# obstacle_avoiding_robot.net
KiCad netlist of a schematic drawn in EAGLE
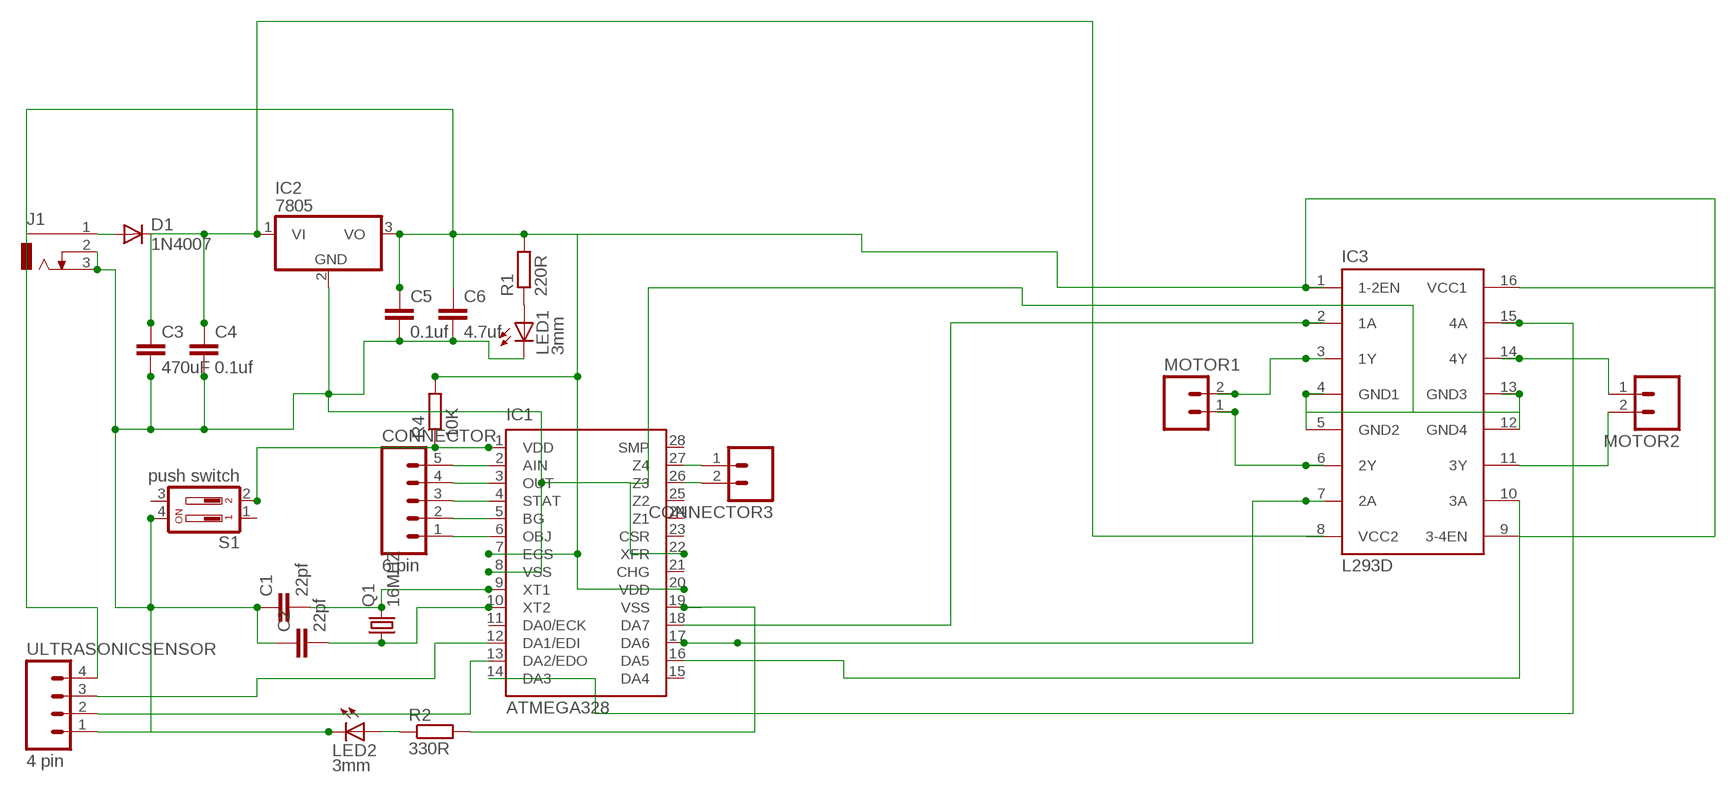
[diagram p0: schematic, sheet 1]

(export (version "E")
  (design (tool "Eeschema 10.0.6"))
  (components
    (comp (ref "C1")
      (value "22pf")
      (footprint "eagle-import:C2.5-2")
      (libsource (lib "eagle-import") (part "C2.5/2"))
    )
    (comp (ref "C2")
      (value "22pf")
      (footprint "eagle-import:C2.5-2")
      (libsource (lib "eagle-import") (part "C2.5/2"))
    )
    (comp (ref "C3")
      (value "470uF")
      (footprint "eagle-import:C2.5-2")
      (libsource (lib "eagle-import") (part "C2.5/2"))
    )
    (comp (ref "C4")
      (value "0.1uf")
      (footprint "eagle-import:C2.5-2")
      (libsource (lib "eagle-import") (part "C2.5/2"))
    )
    (comp (ref "C5")
      (value "0.1uf")
      (footprint "eagle-import:C2.5-2")
      (libsource (lib "eagle-import") (part "C2.5/2"))
    )
    (comp (ref "C6")
      (value "4.7uf")
      (footprint "eagle-import:C2.5-2")
      (libsource (lib "eagle-import") (part "C2.5/2"))
    )
    (comp (ref "CONNECTOR")
      (value "6 pin")
      (footprint "eagle-import:05P")
      (libsource (lib "eagle-import") (part "M05"))
    )
    (comp (ref "CONNECTOR3")
      (value "M02")
      (footprint "eagle-import:02P")
      (fields (field (name "OC_FARNELL") "unknown") (field (name "OC_NEWARK") "unknown"))
      (libsource (lib "eagle-import") (part "M02"))
    )
    (comp (ref "D1")
      (value "1N4007")
      (footprint "eagle-import:DO41-10")
      (libsource (lib "eagle-import") (part "1N4004"))
    )
    (comp (ref "IC1")
      (value "ATMEGA328")
      (footprint "eagle-import:DIL28-3")
      (libsource (lib "eagle-import") (part "QT9701BD"))
    )
    (comp (ref "IC2")
      (value "7805")
      (footprint "eagle-import:TO220V")
      (libsource (lib "eagle-import") (part "78TV6"))
    )
    (comp (ref "IC3")
      (value "L293D")
      (footprint "eagle-import:DIL16")
      (libsource (lib "eagle-import") (part "L293D"))
    )
    (comp (ref "J1")
      (value "DCJ0303")
      (footprint "eagle-import:DCJ0303")
      (libsource (lib "eagle-import") (part "DCJ0303"))
    )
    (comp (ref "LED1")
      (value "3mm")
      (footprint "eagle-import:LED3MM")
      (libsource (lib "eagle-import") (part "LED3MM"))
    )
    (comp (ref "LED2")
      (value "3mm")
      (footprint "eagle-import:LED3MM")
      (libsource (lib "eagle-import") (part "LED3MM"))
    )
    (comp (ref "MOTOR1")
      (value "M02")
      (footprint "eagle-import:02P")
      (fields (field (name "OC_FARNELL") "unknown") (field (name "OC_NEWARK") "unknown"))
      (libsource (lib "eagle-import") (part "M02"))
    )
    (comp (ref "MOTOR2")
      (value "M02")
      (footprint "eagle-import:02P")
      (libsource (lib "eagle-import") (part "M02"))
    )
    (comp (ref "Q1")
      (value "16MHZ")
      (footprint "eagle-import:HC49_S")
      (libsource (lib "eagle-import") (part "CRYSTALHC49S"))
    )
    (comp (ref "R1")
      (value "220R")
      (footprint "eagle-import:0207_10")
      (libsource (lib "eagle-import") (part "R-EU_0207/10"))
    )
    (comp (ref "R2")
      (value "330R")
      (footprint "eagle-import:0207_10")
      (libsource (lib "eagle-import") (part "R-EU_0207/10"))
    )
    (comp (ref "R4")
      (value "10K")
      (footprint "eagle-import:0207_10")
      (libsource (lib "eagle-import") (part "R-EU_0207/10"))
    )
    (comp (ref "S1")
      (value "push switch")
      (footprint "eagle-import:DP-02")
      (fields (field (name "MPN") "MCDP02"))
      (libsource (lib "eagle-import") (part "DP02"))
    )
    (comp (ref "ULTRASONICSENSOR")
      (value "4 pin")
      (footprint "eagle-import:04P")
      (fields (field (name "OC_FARNELL") "unknown") (field (name "OC_NEWARK") "unknown"))
      (libsource (lib "eagle-import") (part "M04"))
    )
  )
  (nets
    (net (code "1") (name "Net-(D1-PadA)") (class "Default")
      (node (ref "D1") (pin "A") (pinfunction "A_A") (pintype "passive"))
      (node (ref "J1") (pin "1") (pinfunction "1_1") (pintype "passive"))
    )
    (net (code "2") (name "Net-(IC1-AIN)") (class "Default")
      (node (ref "CONNECTOR") (pin "5") (pinfunction "5_5") (pintype "passive"))
      (node (ref "IC1") (pin "2") (pinfunction "AIN_2") (pintype "input"))
    )
    (net (code "3") (name "Net-(IC1-BG)") (class "Default")
      (node (ref "CONNECTOR") (pin "2") (pinfunction "2_2") (pintype "passive"))
      (node (ref "IC1") (pin "5") (pinfunction "BG_5") (pintype "input"))
    )
    (net (code "4") (name "Net-(IC1-DA1{slash}EDI)") (class "Default")
      (node (ref "IC1") (pin "12") (pinfunction "DA1/EDI_12") (pintype "output"))
      (node (ref "ULTRASONICSENSOR") (pin "3") (pinfunction "3_3") (pintype "passive"))
    )
    (net (code "5") (name "Net-(IC1-DA2{slash}EDO)") (class "Default")
      (node (ref "IC1") (pin "13") (pinfunction "DA2/EDO_13") (pintype "output"))
      (node (ref "ULTRASONICSENSOR") (pin "2") (pinfunction "2_2") (pintype "passive"))
    )
    (net (code "6") (name "Net-(IC1-DA3)") (class "Default")
      (node (ref "IC1") (pin "14") (pinfunction "DA3_14") (pintype "output"))
      (node (ref "IC3") (pin "15") (pinfunction "4A_15") (pintype "input"))
    )
    (net (code "7") (name "Net-(IC1-DA5)") (class "Default")
      (node (ref "IC1") (pin "16") (pinfunction "DA5_16") (pintype "output"))
      (node (ref "IC3") (pin "10") (pinfunction "3A_10") (pintype "input"))
    )
    (net (code "8") (name "Net-(IC1-DA6)") (class "Default")
      (node (ref "IC1") (pin "17") (pinfunction "DA6_17") (pintype "output"))
      (node (ref "IC3") (pin "7") (pinfunction "2A_7") (pintype "input"))
    )
    (net (code "9") (name "Net-(IC1-DA7)") (class "Default")
      (node (ref "IC1") (pin "18") (pinfunction "DA7_18") (pintype "output"))
      (node (ref "IC3") (pin "2") (pinfunction "1A_2") (pintype "input"))
    )
    (net (code "10") (name "Net-(IC1-ECS)") (class "Default")
      (node (ref "C5") (pin "1") (pinfunction "1_1") (pintype "passive"))
      (node (ref "C6") (pin "1") (pinfunction "1_1") (pintype "passive"))
      (node (ref "IC1") (pin "20") (pinfunction "VDD_20") (pintype "input"))
      (node (ref "IC1") (pin "7") (pinfunction "ECS_7") (pintype "output"))
      (node (ref "IC2") (pin "3") (pinfunction "VO_3") (pintype "passive"))
      (node (ref "IC3") (pin "1") (pinfunction "1-2EN_1") (pintype "input"))
      (node (ref "IC3") (pin "16") (pinfunction "VCC1_16") (pintype "power_in"))
      (node (ref "IC3") (pin "9") (pinfunction "3-4EN_9") (pintype "input"))
      (node (ref "R1") (pin "2") (pinfunction "2_2") (pintype "passive"))
      (node (ref "R4") (pin "2") (pinfunction "2_2") (pintype "passive"))
      (node (ref "ULTRASONICSENSOR") (pin "4") (pinfunction "4_4") (pintype "passive"))
    )
    (net (code "11") (name "Net-(IC1-OBJ)") (class "Default")
      (node (ref "CONNECTOR") (pin "1") (pinfunction "1_1") (pintype "passive"))
      (node (ref "IC1") (pin "6") (pinfunction "OBJ_6") (pintype "input"))
    )
    (net (code "12") (name "Net-(IC1-OUT)") (class "Default")
      (node (ref "CONNECTOR") (pin "4") (pinfunction "4_4") (pintype "passive"))
      (node (ref "IC1") (pin "3") (pinfunction "OUT_3") (pintype "output"))
    )
    (net (code "13") (name "Net-(IC1-STAT)") (class "Default")
      (node (ref "CONNECTOR") (pin "3") (pinfunction "3_3") (pintype "passive"))
      (node (ref "IC1") (pin "4") (pinfunction "STAT_4") (pintype "output"))
    )
    (net (code "14") (name "Net-(IC1-VDD-Pad1)") (class "Default")
      (node (ref "IC1") (pin "1") (pinfunction "VDD_1") (pintype "input"))
      (node (ref "R4") (pin "1") (pinfunction "1_1") (pintype "passive"))
      (node (ref "S1") (pin "2") (pinfunction "2_2") (pintype "passive"))
    )
    (net (code "15") (name "Net-(IC1-VSS-Pad19)") (class "Default")
      (node (ref "IC1") (pin "19") (pinfunction "VSS_19") (pintype "input"))
      (node (ref "R2") (pin "2") (pinfunction "2_2") (pintype "passive"))
    )
    (net (code "16") (name "Net-(IC1-XFR)") (class "Default")
      (node (ref "C1") (pin "1") (pinfunction "1_1") (pintype "passive"))
      (node (ref "C2") (pin "1") (pinfunction "1_1") (pintype "passive"))
      (node (ref "C3") (pin "2") (pinfunction "2_2") (pintype "passive"))
      (node (ref "C4") (pin "2") (pinfunction "2_2") (pintype "passive"))
      (node (ref "C5") (pin "2") (pinfunction "2_2") (pintype "passive"))
      (node (ref "C6") (pin "2") (pinfunction "2_2") (pintype "passive"))
      (node (ref "IC1") (pin "22") (pinfunction "XFR_22") (pintype "output"))
      (node (ref "IC1") (pin "8") (pinfunction "VSS_8") (pintype "input"))
      (node (ref "IC2") (pin "2") (pinfunction "GND_2") (pintype "passive"))
      (node (ref "IC3") (pin "12") (pinfunction "GND4_12") (pintype "power_in"))
      (node (ref "IC3") (pin "13") (pinfunction "GND3_13") (pintype "power_in"))
      (node (ref "IC3") (pin "4") (pinfunction "GND1_4") (pintype "power_in"))
      (node (ref "IC3") (pin "5") (pinfunction "GND2_5") (pintype "power_in"))
      (node (ref "J1") (pin "2") (pinfunction "2_2") (pintype "passive"))
      (node (ref "J1") (pin "3") (pinfunction "3_3") (pintype "passive"))
      (node (ref "LED1") (pin "K") (pinfunction "C_K") (pintype "passive"))
      (node (ref "LED2") (pin "K") (pinfunction "C_K") (pintype "passive"))
      (node (ref "S1") (pin "4") (pinfunction "4_4") (pintype "passive"))
      (node (ref "ULTRASONICSENSOR") (pin "1") (pinfunction "1_1") (pintype "passive"))
    )
    (net (code "17") (name "Net-(IC1-XT1)") (class "Default")
      (node (ref "C1") (pin "2") (pinfunction "2_2") (pintype "passive"))
      (node (ref "IC1") (pin "9") (pinfunction "XT1_9") (pintype "input"))
      (node (ref "Q1") (pin "2") (pinfunction "2_2") (pintype "passive"))
    )
    (net (code "18") (name "Net-(IC1-XT2)") (class "Default")
      (node (ref "C2") (pin "2") (pinfunction "2_2") (pintype "passive"))
      (node (ref "IC1") (pin "10") (pinfunction "XT2_10") (pintype "output"))
      (node (ref "Q1") (pin "1") (pinfunction "1_1") (pintype "passive"))
    )
    (net (code "19") (name "Net-(IC1-Z3)") (class "Default")
      (node (ref "CONNECTOR3") (pin "2") (pinfunction "2_2") (pintype "passive"))
      (node (ref "IC1") (pin "26") (pinfunction "Z3_26") (pintype "output"))
    )
    (net (code "20") (name "Net-(IC1-Z4)") (class "Default")
      (node (ref "CONNECTOR3") (pin "1") (pinfunction "1_1") (pintype "passive"))
      (node (ref "IC1") (pin "27") (pinfunction "Z4_27") (pintype "output"))
    )
    (net (code "21") (name "Net-(IC2-VI)") (class "Default")
      (node (ref "C3") (pin "1") (pinfunction "1_1") (pintype "passive"))
      (node (ref "C4") (pin "1") (pinfunction "1_1") (pintype "passive"))
      (node (ref "D1") (pin "C") (pinfunction "C_C") (pintype "passive"))
      (node (ref "IC2") (pin "1") (pinfunction "VI_1") (pintype "input"))
      (node (ref "IC3") (pin "8") (pinfunction "VCC2_8") (pintype "power_in"))
    )
    (net (code "22") (name "Net-(IC3-1Y)") (class "Default")
      (node (ref "IC3") (pin "3") (pinfunction "1Y_3") (pintype "output"))
      (node (ref "MOTOR1") (pin "2") (pinfunction "2_2") (pintype "passive"))
    )
    (net (code "23") (name "Net-(IC3-2Y)") (class "Default")
      (node (ref "IC3") (pin "6") (pinfunction "2Y_6") (pintype "output"))
      (node (ref "MOTOR1") (pin "1") (pinfunction "1_1") (pintype "passive"))
    )
    (net (code "24") (name "Net-(IC3-3Y)") (class "Default")
      (node (ref "IC3") (pin "11") (pinfunction "3Y_11") (pintype "output"))
      (node (ref "MOTOR2") (pin "2") (pinfunction "2_2") (pintype "passive"))
    )
    (net (code "25") (name "Net-(IC3-4Y)") (class "Default")
      (node (ref "IC3") (pin "14") (pinfunction "4Y_14") (pintype "output"))
      (node (ref "MOTOR2") (pin "1") (pinfunction "1_1") (pintype "passive"))
    )
    (net (code "26") (name "Net-(LED1-PadA)") (class "Default")
      (node (ref "LED1") (pin "A") (pinfunction "A_A") (pintype "passive"))
      (node (ref "R1") (pin "1") (pinfunction "1_1") (pintype "passive"))
    )
    (net (code "27") (name "Net-(LED2-PadA)") (class "Default")
      (node (ref "LED2") (pin "A") (pinfunction "A_A") (pintype "passive"))
      (node (ref "R2") (pin "1") (pinfunction "1_1") (pintype "passive"))
    )
    (net (code "28") (name "unconnected-(IC1-CHG-Pad21)") (class "Default")
      (node (ref "IC1") (pin "21") (pinfunction "CHG_21") (pintype "output"))
    )
    (net (code "29") (name "unconnected-(IC1-CSR-Pad23)") (class "Default")
      (node (ref "IC1") (pin "23") (pinfunction "CSR_23") (pintype "output"))
    )
    (net (code "30") (name "unconnected-(IC1-DA0{slash}ECK-Pad11)") (class "Default")
      (node (ref "IC1") (pin "11") (pinfunction "DA0/ECK_11") (pintype "output"))
    )
    (net (code "31") (name "unconnected-(IC1-DA4-Pad15)") (class "Default")
      (node (ref "IC1") (pin "15") (pinfunction "DA4_15") (pintype "output"))
    )
    (net (code "32") (name "unconnected-(IC1-SMP-Pad28)") (class "Default")
      (node (ref "IC1") (pin "28") (pinfunction "SMP_28") (pintype "output"))
    )
    (net (code "33") (name "unconnected-(IC1-Z1-Pad24)") (class "Default")
      (node (ref "IC1") (pin "24") (pinfunction "Z1_24") (pintype "output"))
    )
    (net (code "34") (name "unconnected-(IC1-Z2-Pad25)") (class "Default")
      (node (ref "IC1") (pin "25") (pinfunction "Z2_25") (pintype "output"))
    )
    (net (code "35") (name "unconnected-(S1-Pad1)") (class "Default")
      (node (ref "S1") (pin "1") (pinfunction "1_1") (pintype "passive"))
    )
    (net (code "36") (name "unconnected-(S1-Pad3)") (class "Default")
      (node (ref "S1") (pin "3") (pinfunction "3_3") (pintype "passive"))
    )
  )
)
